# Switches.net
KiCad netlist of a schematic drawn in Altium Designer
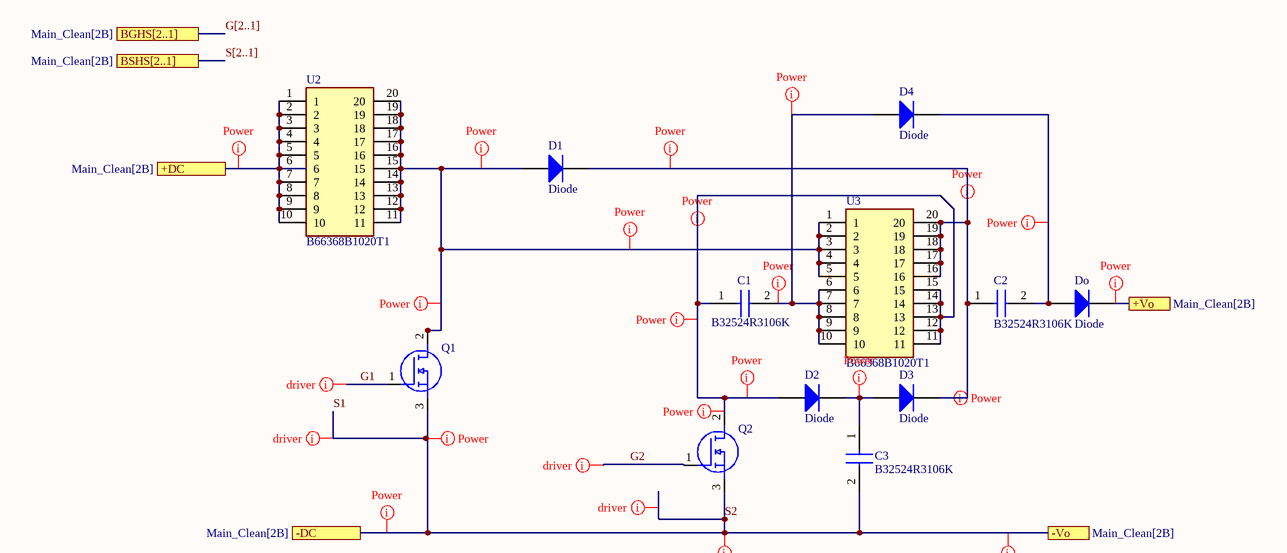
[diagram p0: Switches.SchDoc]

(export (version "E")
  (design (tool "Eeschema 10.0.6"))
  (components
    (comp (ref "C1")
      (value "B32524R3106K")
      (footprint "SamacSys:B32524R3106K")
      (description "Capacitor")
      (fields (field (name "MOUSER PART NUMBER") "871-B32524R3106K"))
      (libsource (lib "SamacSys") (part "B32524R3106K"))
    )
    (comp (ref "C2")
      (value "B32524R3106K")
      (footprint "SamacSys:B32524R3106K")
      (description "Capacitor")
      (fields (field (name "MOUSER PART NUMBER") "871-B32524R3106K"))
      (libsource (lib "SamacSys") (part "B32524R3106K"))
    )
    (comp (ref "C3")
      (value "B32524R3106K")
      (footprint "SamacSys:B32524R3106K")
      (description "Capacitor")
      (fields (field (name "MOUSER PART NUMBER") "871-B32524R3106K"))
      (libsource (lib "SamacSys") (part "B32524R3106K"))
    )
    (comp (ref "D1")
      (value "Diode")
      (footprint "Dpak")
      (description "Default Diode")
      (fields (field (name "PUBLISHER") "Altium Limited"))
      (libsource (lib "Miscellaneous Devices") (part "Diode"))
    )
    (comp (ref "D2")
      (value "Diode")
      (footprint "Dpak")
      (description "Default Diode")
      (fields (field (name "PUBLISHER") "Altium Limited"))
      (libsource (lib "Miscellaneous Devices") (part "Diode"))
    )
    (comp (ref "D3")
      (value "Diode")
      (footprint "Dpak")
      (description "Default Diode")
      (fields (field (name "PUBLISHER") "Altium Limited"))
      (libsource (lib "Miscellaneous Devices") (part "Diode"))
    )
    (comp (ref "D4")
      (value "Diode")
      (footprint "Dpak")
      (description "Default Diode")
      (fields (field (name "PUBLISHER") "Altium Limited"))
      (libsource (lib "Miscellaneous Devices") (part "Diode"))
    )
    (comp (ref "Do")
      (value "Diode")
      (footprint "Dpak")
      (description "Default Diode")
      (fields (field (name "PUBLISHER") "Altium Limited"))
      (libsource (lib "Miscellaneous Devices") (part "Diode"))
    )
    (comp (ref "Q1")
      (value "IPB048N15N5LFATMA1")
      (footprint "D2PAK")
      (description "Trans MOSFET N-CH 150V 120A 3-Pin(2+Tab) D2PAK T/R")
      (fields (field (name "MOUSER PART NUMBER") "726-IPB048N15N5LF"))
      (libsource (lib "Saeed") (part "IPB048N15N5LFATMA1"))
    )
    (comp (ref "Q2")
      (value "IPB048N15N5LFATMA1")
      (footprint "D2PAK")
      (description "Trans MOSFET N-CH 150V 120A 3-Pin(2+Tab) D2PAK T/R")
      (fields (field (name "MOUSER PART NUMBER") "726-IPB048N15N5LF"))
      (libsource (lib "Saeed") (part "IPB048N15N5LFATMA1"))
    )
    (comp (ref "U2")
      (value "B66368B1020T1")
      (footprint "SamacSys:B66368B1020T1")
      (description "Undefined or Miscellaneous")
      (fields (field (name "MOUSER PART NUMBER") "871-B66368B1020T1"))
      (libsource (lib "*") (part "B66368B1020T1"))
    )
    (comp (ref "U3")
      (value "B66368B1020T1")
      (footprint "SamacSys:B66368B1020T1")
      (description "Undefined or Miscellaneous")
      (fields (field (name "MOUSER PART NUMBER") "871-B66368B1020T1"))
      (libsource (lib "*") (part "B66368B1020T1"))
    )
  )
  (nets
    (net (code "1") (name "/+DC") (class "Default")
      (node (ref "U2") (pin "1") (pinfunction "1_1") (pintype "passive"))
      (node (ref "U2") (pin "10") (pinfunction "10_10") (pintype "passive"))
      (node (ref "U2") (pin "2") (pinfunction "2_2") (pintype "passive"))
      (node (ref "U2") (pin "3") (pinfunction "3_3") (pintype "passive"))
      (node (ref "U2") (pin "4") (pinfunction "4_4") (pintype "passive"))
      (node (ref "U2") (pin "5") (pinfunction "5_5") (pintype "passive"))
      (node (ref "U2") (pin "6") (pinfunction "6_6") (pintype "passive"))
      (node (ref "U2") (pin "7") (pinfunction "7_7") (pintype "passive"))
      (node (ref "U2") (pin "8") (pinfunction "8_8") (pintype "passive"))
      (node (ref "U2") (pin "9") (pinfunction "9_9") (pintype "passive"))
    )
    (net (code "2") (name "/+Vo") (class "Default")
      (node (ref "Do") (pin "2") (pinfunction "K_2") (pintype "passive"))
    )
    (net (code "3") (name "/G1") (class "Default")
      (node (ref "Q1") (pin "1") (pinfunction "G_1") (pintype "passive"))
    )
    (net (code "4") (name "/G2") (class "Default")
      (node (ref "Q2") (pin "1") (pinfunction "G_1") (pintype "passive"))
    )
    (net (code "6") (name "/S2") (class "Default")
      (node (ref "C3") (pin "2") (pinfunction "2_2") (pintype "passive"))
      (node (ref "Q1") (pin "3") (pinfunction "S_3") (pintype "passive"))
      (node (ref "Q2") (pin "3") (pinfunction "S_3") (pintype "passive"))
    )
    (net (code "8") (name "Net-(D1-A)") (class "Default")
      (node (ref "D1") (pin "1") (pinfunction "A_1") (pintype "passive"))
      (node (ref "Q1") (pin "2") (pinfunction "D_2") (pintype "passive"))
      (node (ref "U2") (pin "11") (pinfunction "11_11") (pintype "passive"))
      (node (ref "U2") (pin "12") (pinfunction "12_12") (pintype "passive"))
      (node (ref "U2") (pin "13") (pinfunction "13_13") (pintype "passive"))
      (node (ref "U2") (pin "14") (pinfunction "14_14") (pintype "passive"))
      (node (ref "U2") (pin "15") (pinfunction "15_15") (pintype "passive"))
      (node (ref "U2") (pin "16") (pinfunction "16_16") (pintype "passive"))
      (node (ref "U2") (pin "17") (pinfunction "17_17") (pintype "passive"))
      (node (ref "U2") (pin "18") (pinfunction "18_18") (pintype "passive"))
      (node (ref "U2") (pin "19") (pinfunction "19_19") (pintype "passive"))
      (node (ref "U2") (pin "20") (pinfunction "20_20") (pintype "passive"))
      (node (ref "U3") (pin "1") (pinfunction "1_1") (pintype "passive"))
      (node (ref "U3") (pin "2") (pinfunction "2_2") (pintype "passive"))
      (node (ref "U3") (pin "3") (pinfunction "3_3") (pintype "passive"))
      (node (ref "U3") (pin "4") (pinfunction "4_4") (pintype "passive"))
      (node (ref "U3") (pin "5") (pinfunction "5_5") (pintype "passive"))
    )
    (net (code "9") (name "Net-(D1-K)") (class "Default")
      (node (ref "C2") (pin "1") (pinfunction "1_1") (pintype "passive"))
      (node (ref "D1") (pin "2") (pinfunction "K_2") (pintype "passive"))
      (node (ref "D3") (pin "2") (pinfunction "K_2") (pintype "passive"))
      (node (ref "U3") (pin "16") (pinfunction "16_16") (pintype "passive"))
      (node (ref "U3") (pin "17") (pinfunction "17_17") (pintype "passive"))
      (node (ref "U3") (pin "18") (pinfunction "18_18") (pintype "passive"))
      (node (ref "U3") (pin "19") (pinfunction "19_19") (pintype "passive"))
      (node (ref "U3") (pin "20") (pinfunction "20_20") (pintype "passive"))
    )
    (net (code "10") (name "Net-(D2-A)") (class "Default")
      (node (ref "C1") (pin "1") (pinfunction "1_1") (pintype "passive"))
      (node (ref "D2") (pin "1") (pinfunction "A_1") (pintype "passive"))
      (node (ref "Q2") (pin "2") (pinfunction "D_2") (pintype "passive"))
      (node (ref "U3") (pin "11") (pinfunction "11_11") (pintype "passive"))
      (node (ref "U3") (pin "12") (pinfunction "12_12") (pintype "passive"))
      (node (ref "U3") (pin "13") (pinfunction "13_13") (pintype "passive"))
      (node (ref "U3") (pin "14") (pinfunction "14_14") (pintype "passive"))
      (node (ref "U3") (pin "15") (pinfunction "15_15") (pintype "passive"))
    )
    (net (code "11") (name "Net-(D2-K)") (class "Default")
      (node (ref "C3") (pin "1") (pinfunction "1_1") (pintype "passive"))
      (node (ref "D2") (pin "2") (pinfunction "K_2") (pintype "passive"))
      (node (ref "D3") (pin "1") (pinfunction "A_1") (pintype "passive"))
    )
    (net (code "12") (name "Net-(D4-A)") (class "Default")
      (node (ref "C1") (pin "2") (pinfunction "2_2") (pintype "passive"))
      (node (ref "D4") (pin "1") (pinfunction "A_1") (pintype "passive"))
      (node (ref "U3") (pin "10") (pinfunction "10_10") (pintype "passive"))
      (node (ref "U3") (pin "6") (pinfunction "6_6") (pintype "passive"))
      (node (ref "U3") (pin "7") (pinfunction "7_7") (pintype "passive"))
      (node (ref "U3") (pin "8") (pinfunction "8_8") (pintype "passive"))
      (node (ref "U3") (pin "9") (pinfunction "9_9") (pintype "passive"))
    )
    (net (code "13") (name "Net-(D4-K)") (class "Default")
      (node (ref "C2") (pin "2") (pinfunction "2_2") (pintype "passive"))
      (node (ref "D4") (pin "2") (pinfunction "K_2") (pintype "passive"))
      (node (ref "Do") (pin "1") (pinfunction "A_1") (pintype "passive"))
    )
  )
)
